# A2235-H.net
KiCad netlist of a schematic drawn in EAGLE
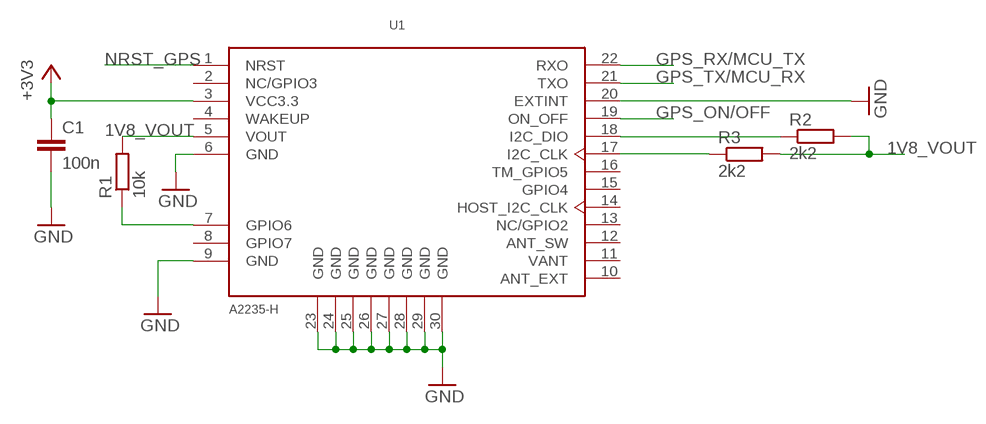
[diagram p0: schematic, sheet 1]

(export (version "E")
  (design (tool "Eeschema 10.0.6"))
  (components
    (comp (ref "C1")
      (value "100n")
      (footprint "eagle-import:C0805")
      (libsource (lib "eagle-import") (part "C-EUC0805"))
    )
    (comp (ref "R1")
      (value "10k")
      (footprint "eagle-import:R0805")
      (libsource (lib "eagle-import") (part "R-EU_R0805"))
    )
    (comp (ref "R2")
      (value "2k2")
      (footprint "eagle-import:R0805")
      (libsource (lib "eagle-import") (part "R-EU_R0805"))
    )
    (comp (ref "R3")
      (value "2k2")
      (footprint "eagle-import:R0805")
      (libsource (lib "eagle-import") (part "R-EU_R0805"))
    )
    (comp (ref "U1")
      (value "A2235-H")
      (footprint "eagle-import:XCVR_A2235-H")
      (fields (field (name "MF") "Maestro Wireless") (field (name "MP") "A2235H"))
      (libsource (lib "eagle-import") (part "A2235-H"))
    )
  )
  (nets
    (net (code "1") (name "+3V3") (class "Default")
      (node (ref "C1") (pin "1") (pinfunction "1_1") (pintype "passive"))
      (node (ref "U1") (pin "3") (pinfunction "VCC3.3_3") (pintype "power_in"))
    )
    (net (code "2") (name "/1V8_VOUT") (class "Default")
      (node (ref "R1") (pin "2") (pinfunction "2_2") (pintype "passive"))
      (node (ref "R2") (pin "2") (pinfunction "2_2") (pintype "passive"))
      (node (ref "R3") (pin "2") (pinfunction "2_2") (pintype "passive"))
      (node (ref "U1") (pin "5") (pinfunction "VOUT_5") (pintype "output"))
    )
    (net (code "3") (name "/GPS_ON{slash}OFF") (class "Default")
      (node (ref "U1") (pin "19") (pinfunction "ON_OFF_19") (pintype "input"))
    )
    (net (code "4") (name "/GPS_RX{slash}MCU_TX") (class "Default")
      (node (ref "U1") (pin "22") (pinfunction "RXO_22") (pintype "input"))
    )
    (net (code "5") (name "/GPS_TX{slash}MCU_RX") (class "Default")
      (node (ref "U1") (pin "21") (pinfunction "TXO_21") (pintype "output"))
    )
    (net (code "6") (name "/NRST_GPS") (class "Default")
      (node (ref "U1") (pin "1") (pinfunction "NRST_1") (pintype "input"))
    )
    (net (code "7") (name "/VANT") (class "Default")
      (node (ref "U1") (pin "11") (pinfunction "VANT_11") (pintype "power_in"))
    )
    (net (code "8") (name "GND") (class "Default")
      (node (ref "C1") (pin "2") (pinfunction "2_2") (pintype "passive"))
      (node (ref "U1") (pin "20") (pinfunction "EXTINT_20") (pintype "input"))
      (node (ref "U1") (pin "23") (pinfunction "GND_23") (pintype "power_in"))
      (node (ref "U1") (pin "24") (pinfunction "GND_24") (pintype "power_in"))
      (node (ref "U1") (pin "25") (pinfunction "GND_25") (pintype "power_in"))
      (node (ref "U1") (pin "26") (pinfunction "GND_26") (pintype "power_in"))
      (node (ref "U1") (pin "27") (pinfunction "GND_27") (pintype "power_in"))
      (node (ref "U1") (pin "28") (pinfunction "GND_28") (pintype "power_in"))
      (node (ref "U1") (pin "29") (pinfunction "GND_29") (pintype "power_in"))
      (node (ref "U1") (pin "30") (pinfunction "GND_30") (pintype "power_in"))
      (node (ref "U1") (pin "6") (pinfunction "GND_6") (pintype "power_in"))
      (node (ref "U1") (pin "9") (pinfunction "GND_9") (pintype "power_in"))
    )
    (net (code "9") (name "Net-(U1-GPIO6)") (class "Default")
      (node (ref "R1") (pin "1") (pinfunction "1_1") (pintype "passive"))
      (node (ref "U1") (pin "7") (pinfunction "GPIO6_7") (pintype "input"))
    )
    (net (code "10") (name "Net-(U1-I2C_CLK)") (class "Default")
      (node (ref "R3") (pin "1") (pinfunction "1_1") (pintype "passive"))
      (node (ref "U1") (pin "17") (pinfunction "I2C_CLK_17") (pintype "bidirectional"))
    )
    (net (code "11") (name "Net-(U1-I2C_DIO)") (class "Default")
      (node (ref "R2") (pin "1") (pinfunction "1_1") (pintype "passive"))
      (node (ref "U1") (pin "18") (pinfunction "I2C_DIO_18") (pintype "bidirectional"))
    )
    (net (code "12") (name "unconnected-(U1-ANT_EXT-Pad10)") (class "Default")
      (node (ref "U1") (pin "10") (pinfunction "ANT_EXT_10") (pintype "input"))
    )
    (net (code "13") (name "unconnected-(U1-ANT_SW-Pad12)") (class "Default")
      (node (ref "U1") (pin "12") (pinfunction "ANT_SW_12") (pintype "input"))
    )
    (net (code "14") (name "unconnected-(U1-GPIO4-Pad15)") (class "Default")
      (node (ref "U1") (pin "15") (pinfunction "GPIO4_15") (pintype "input"))
    )
    (net (code "15") (name "unconnected-(U1-GPIO7-Pad8)") (class "Default")
      (node (ref "U1") (pin "8") (pinfunction "GPIO7_8") (pintype "input"))
    )
    (net (code "16") (name "unconnected-(U1-HOST_I2C_CLK-Pad14)") (class "Default")
      (node (ref "U1") (pin "14") (pinfunction "HOST_I2C_CLK_14") (pintype "bidirectional"))
    )
    (net (code "17") (name "unconnected-(U1-NC{slash}GPIO2-Pad13)") (class "Default")
      (node (ref "U1") (pin "13") (pinfunction "NC/GPIO2_13") (pintype "bidirectional"))
    )
    (net (code "18") (name "unconnected-(U1-NC{slash}GPIO3-Pad2)") (class "Default")
      (node (ref "U1") (pin "2") (pinfunction "NC/GPIO3_2") (pintype "bidirectional"))
    )
    (net (code "19") (name "unconnected-(U1-TM_GPIO5-Pad16)") (class "Default")
      (node (ref "U1") (pin "16") (pinfunction "TM_GPIO5_16") (pintype "output"))
    )
    (net (code "20") (name "unconnected-(U1-WAKEUP-Pad4)") (class "Default")
      (node (ref "U1") (pin "4") (pinfunction "WAKEUP_4") (pintype "output"))
    )
  )
)
